# Power.net
KiCad netlist of a schematic drawn in Altium Designer
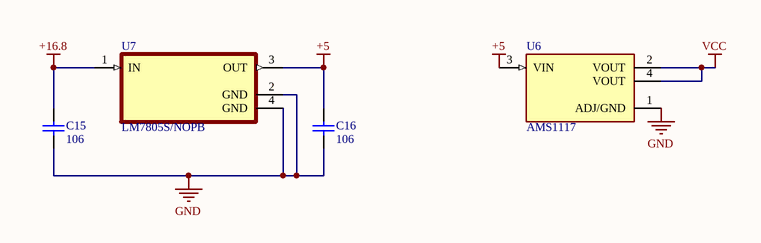
[diagram p0: Power.SchDoc]

(export (version "E")
  (design (tool "Eeschema 10.0.6"))
  (components
    (comp (ref "C15")
      (value "106")
      (footprint "tu 0603")
      (description "Dán")
      (libsource (lib "Tu dien") (part "Tu 0603 106 16V 20%"))
    )
    (comp (ref "C16")
      (value "106")
      (footprint "tu 0603")
      (description "Dán")
      (libsource (lib "Tu dien") (part "Tu 0603 106 16V 20%"))
    )
    (comp (ref "U6")
      (value "AMS1117")
      (footprint "SOT229P700X180-4N")
      (description "1A LOW DROPOUT VOLTAGE REGULATOR SOT-223")
      (fields (field (name "MF") "Advanced Monolithic Systems"))
      (libsource (lib "AMS1117") (part "AMS1117"))
    )
    (comp (ref "U7")
      (value "LM7805S/NOPB")
      (footprint "TO254P1524X483-4N")
      (description "1.5-A, 30-V, linear voltage regulator")
      (fields (field (name "MF") "Texas Instruments"))
      (libsource (lib "LM7805S_NOPB") (part "LM7805S/NOPB"))
    )
  )
  (nets
    (net (code "1") (name "+5") (class "Default")
      (node (ref "C16") (pin "1") (pinfunction "1_1") (pintype "passive"))
      (node (ref "U6") (pin "3") (pinfunction "VIN_3") (pintype "input"))
      (node (ref "U7") (pin "3") (pinfunction "OUT_3") (pintype "output"))
    )
    (net (code "2") (name "+16.8") (class "Default")
      (node (ref "C15") (pin "1") (pinfunction "1_1") (pintype "passive"))
      (node (ref "U7") (pin "1") (pinfunction "IN_1") (pintype "input"))
    )
    (net (code "3") (name "GND") (class "Default")
      (node (ref "C15") (pin "2") (pinfunction "2_2") (pintype "passive"))
      (node (ref "C16") (pin "2") (pinfunction "2_2") (pintype "passive"))
      (node (ref "U6") (pin "1") (pinfunction "ADJ/GND_1") (pintype "power_in"))
      (node (ref "U7") (pin "2") (pinfunction "GND_2") (pintype "power_in"))
      (node (ref "U7") (pin "4") (pinfunction "GND_4") (pintype "power_in"))
    )
    (net (code "4") (name "VCC") (class "Default")
      (node (ref "U6") (pin "2") (pinfunction "VOUT_2") (pintype "passive"))
      (node (ref "U6") (pin "4") (pinfunction "VOUT_4") (pintype "passive"))
    )
  )
)
